# SlippiBoardRev2.net
KiCad netlist of a schematic drawn in EAGLE
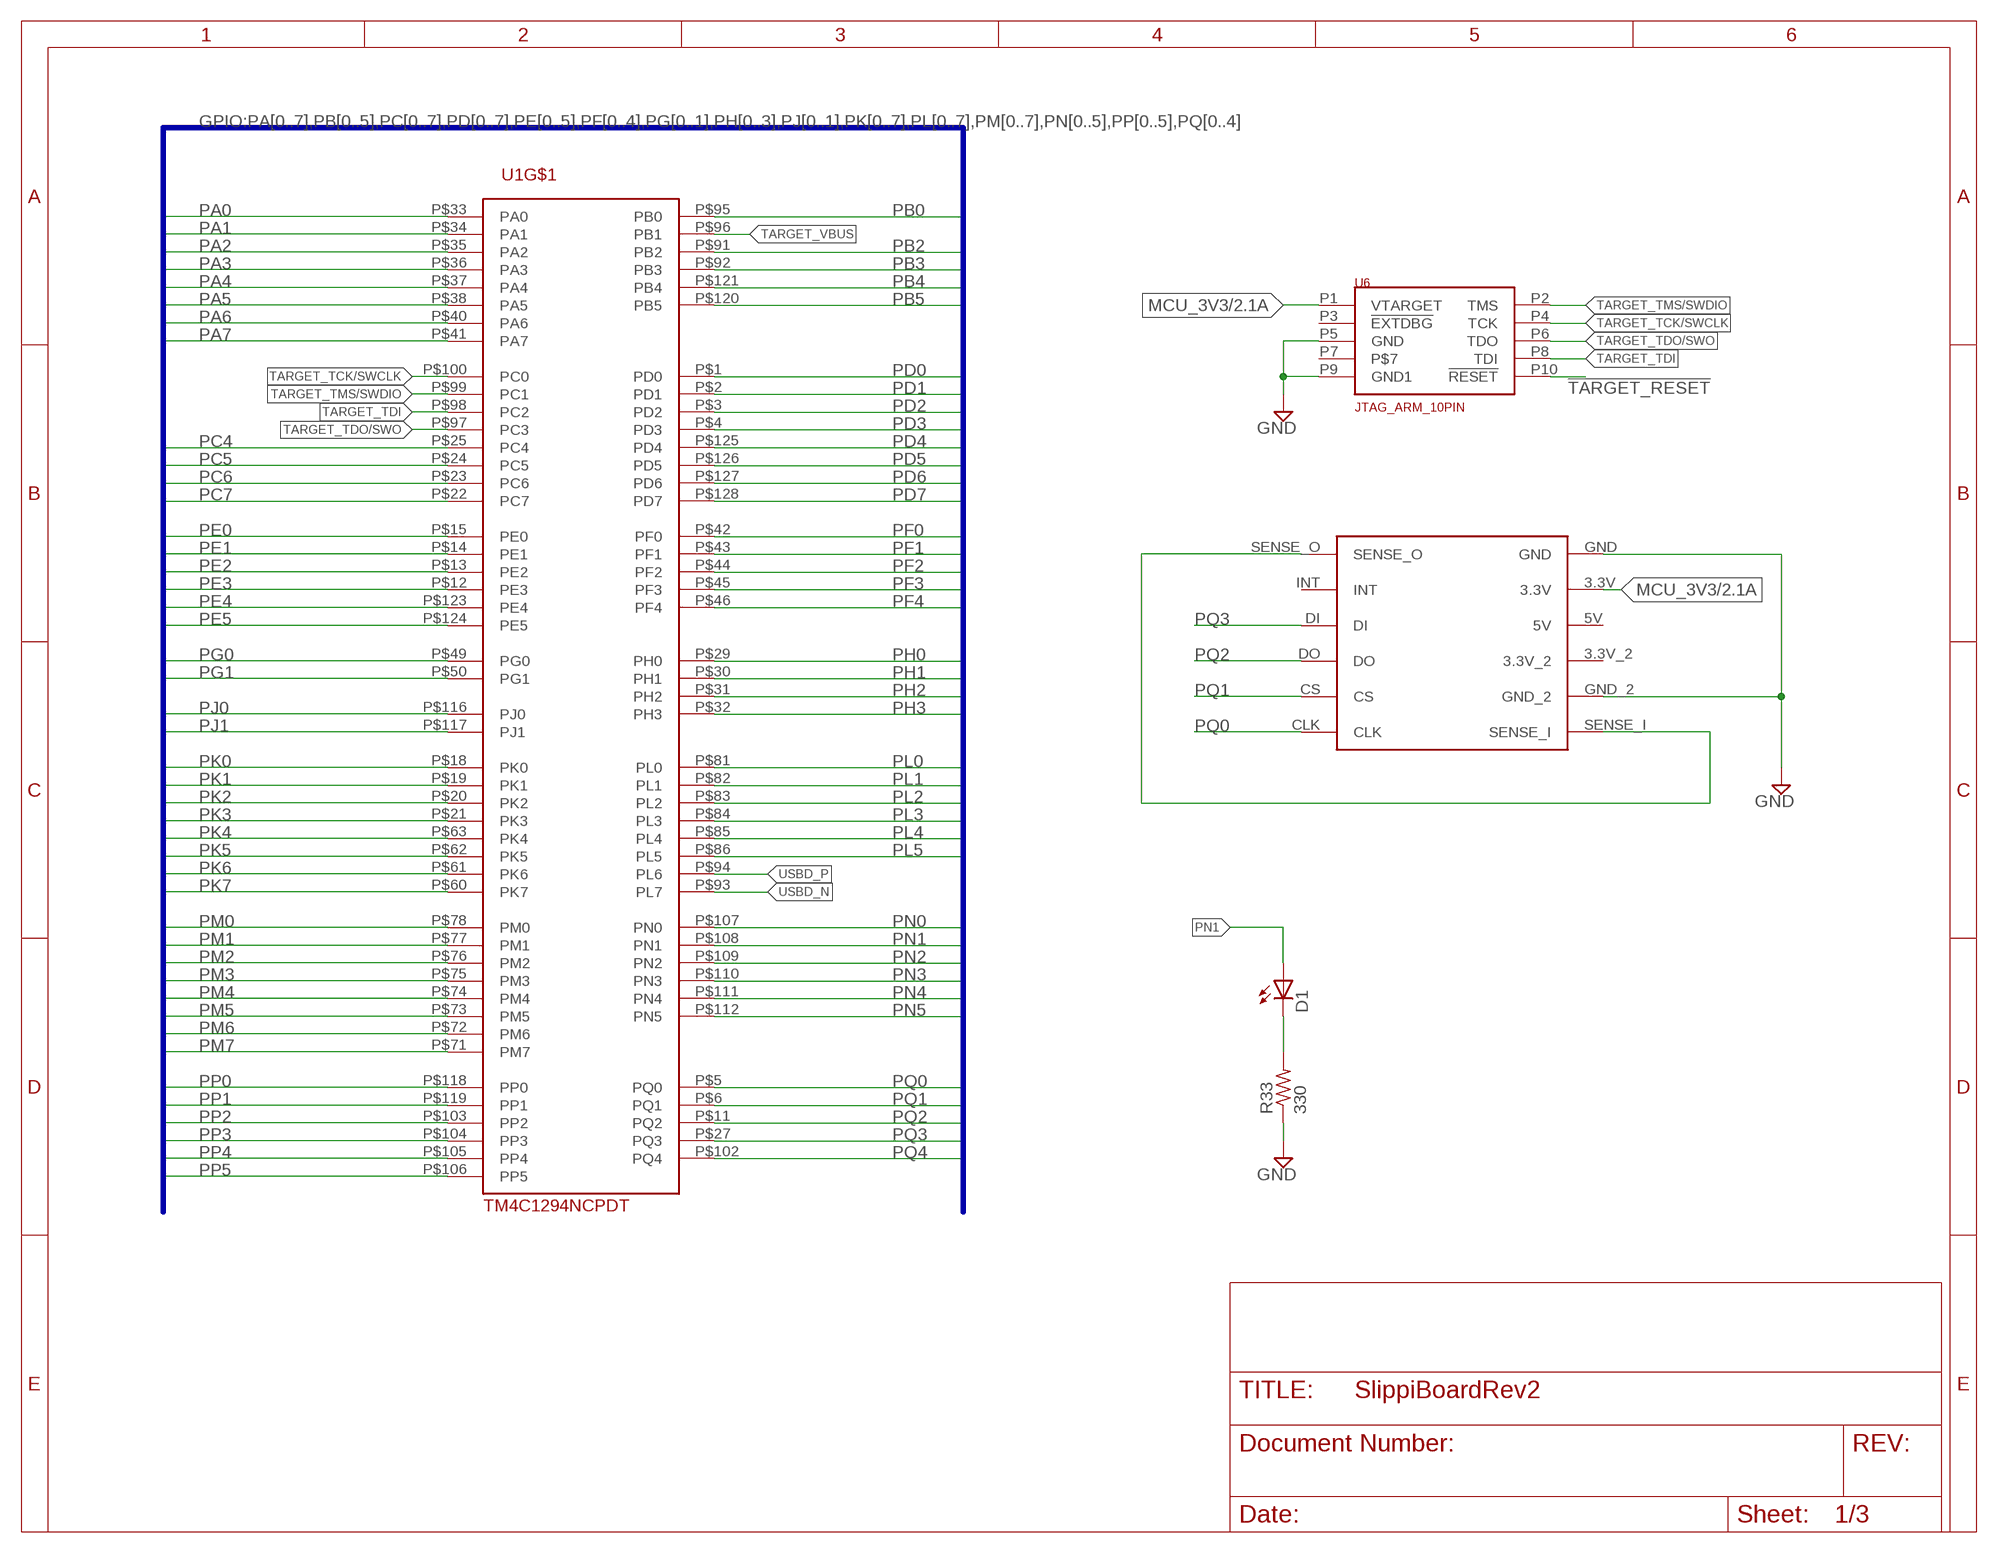
[diagram p0: schematic, sheet 1]
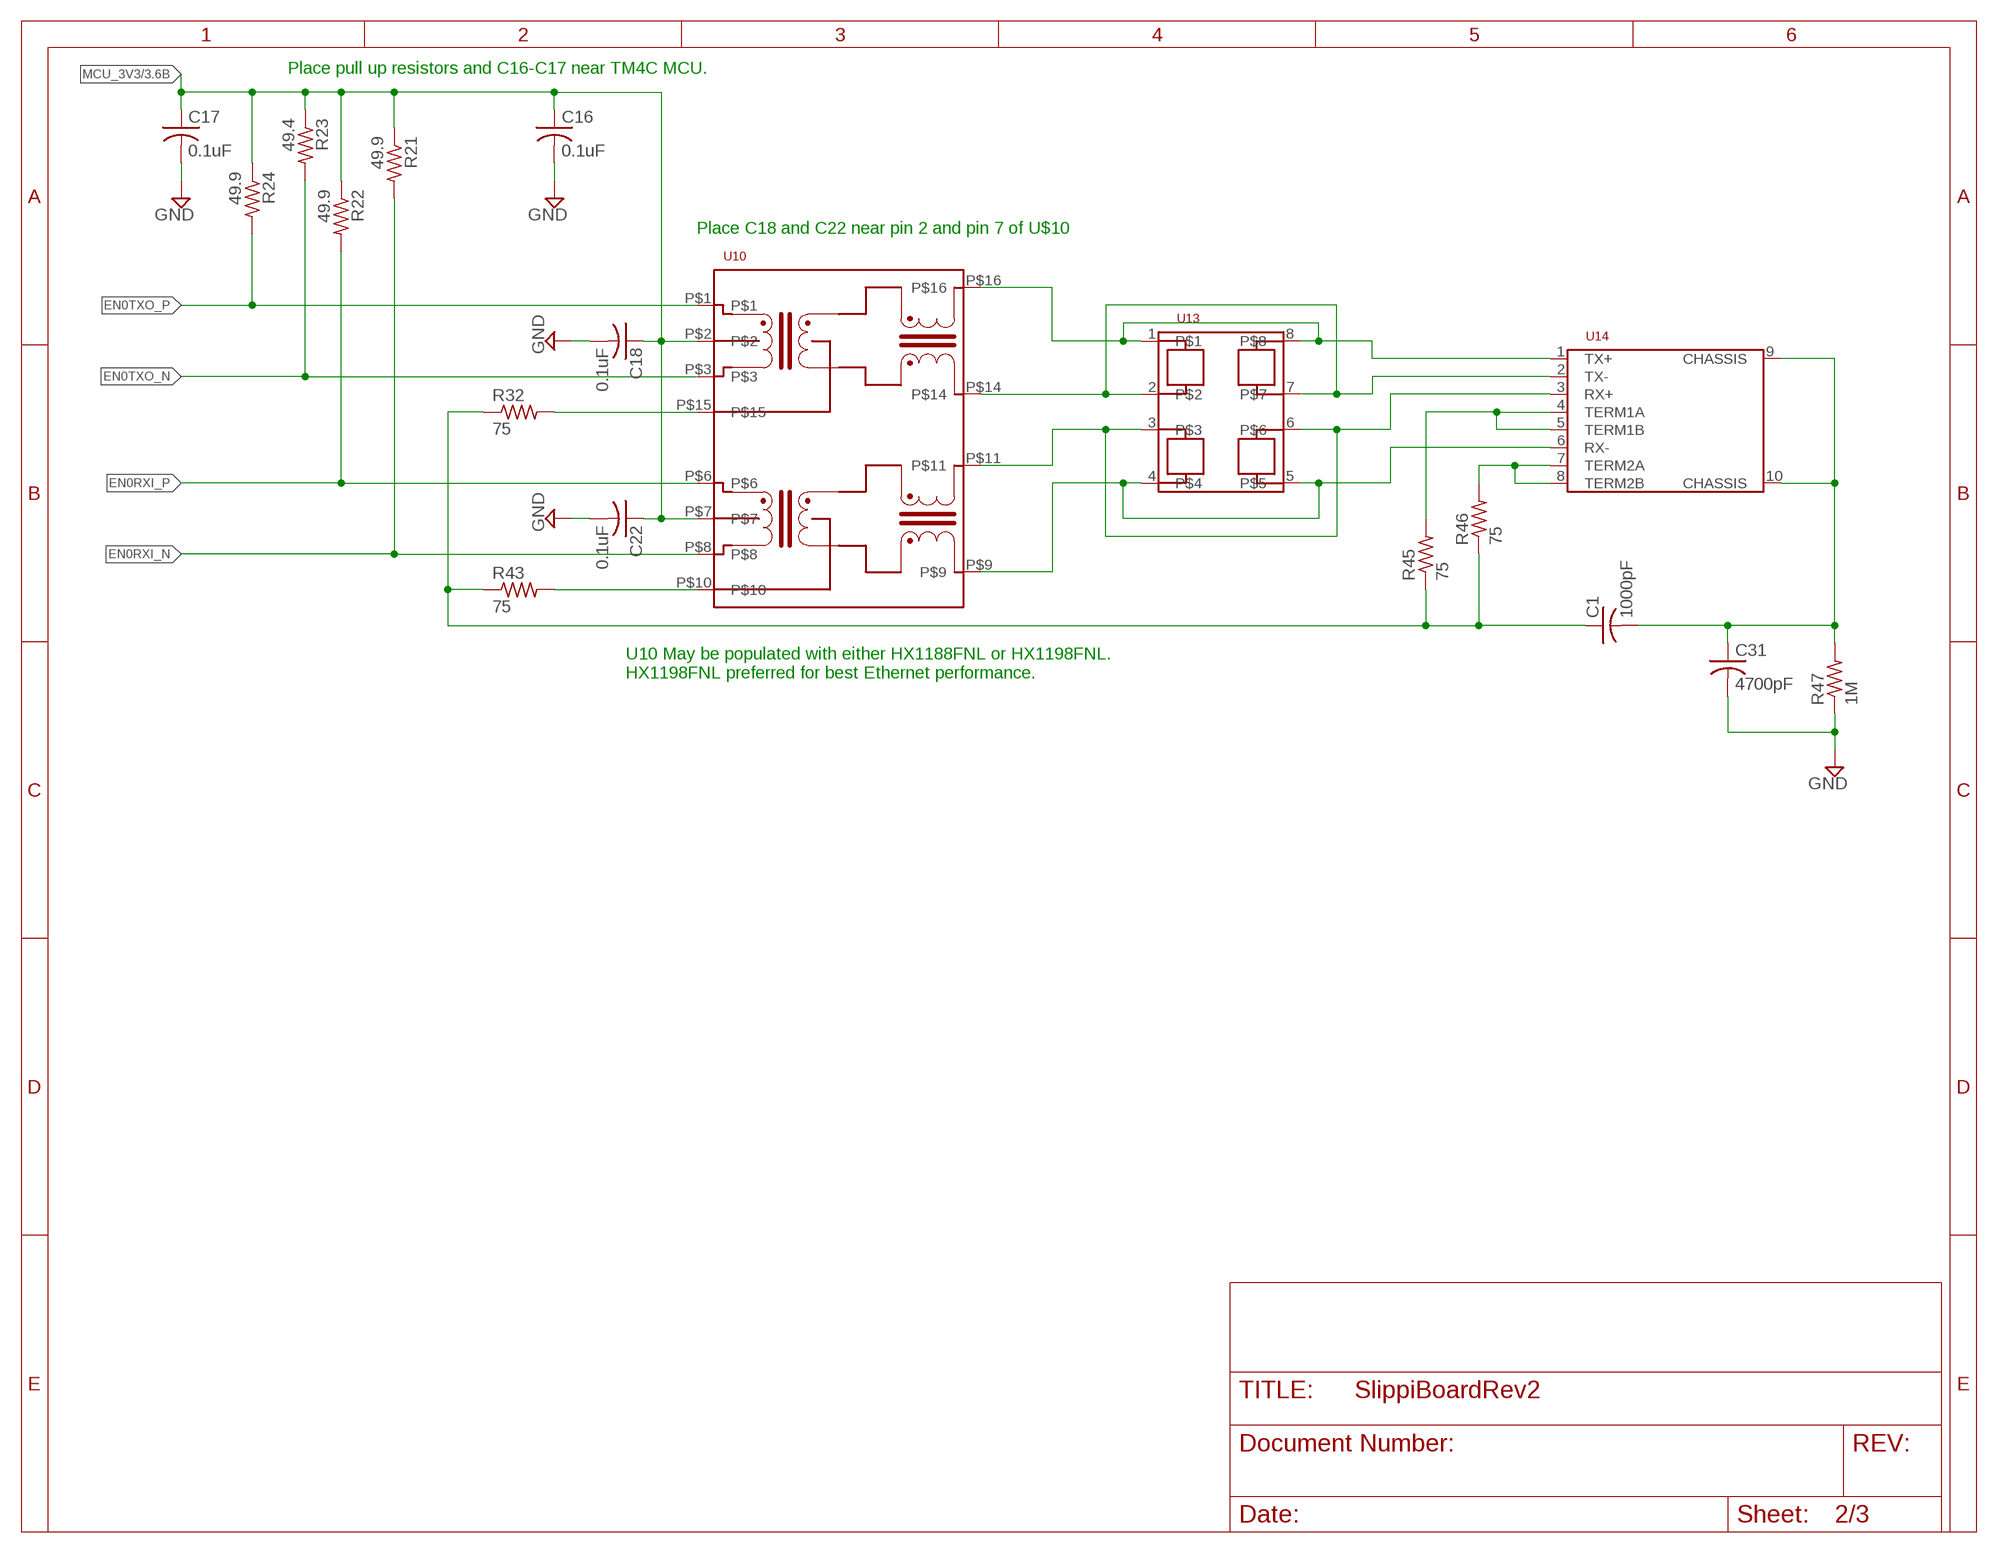
[diagram p1: schematic, sheet 2]
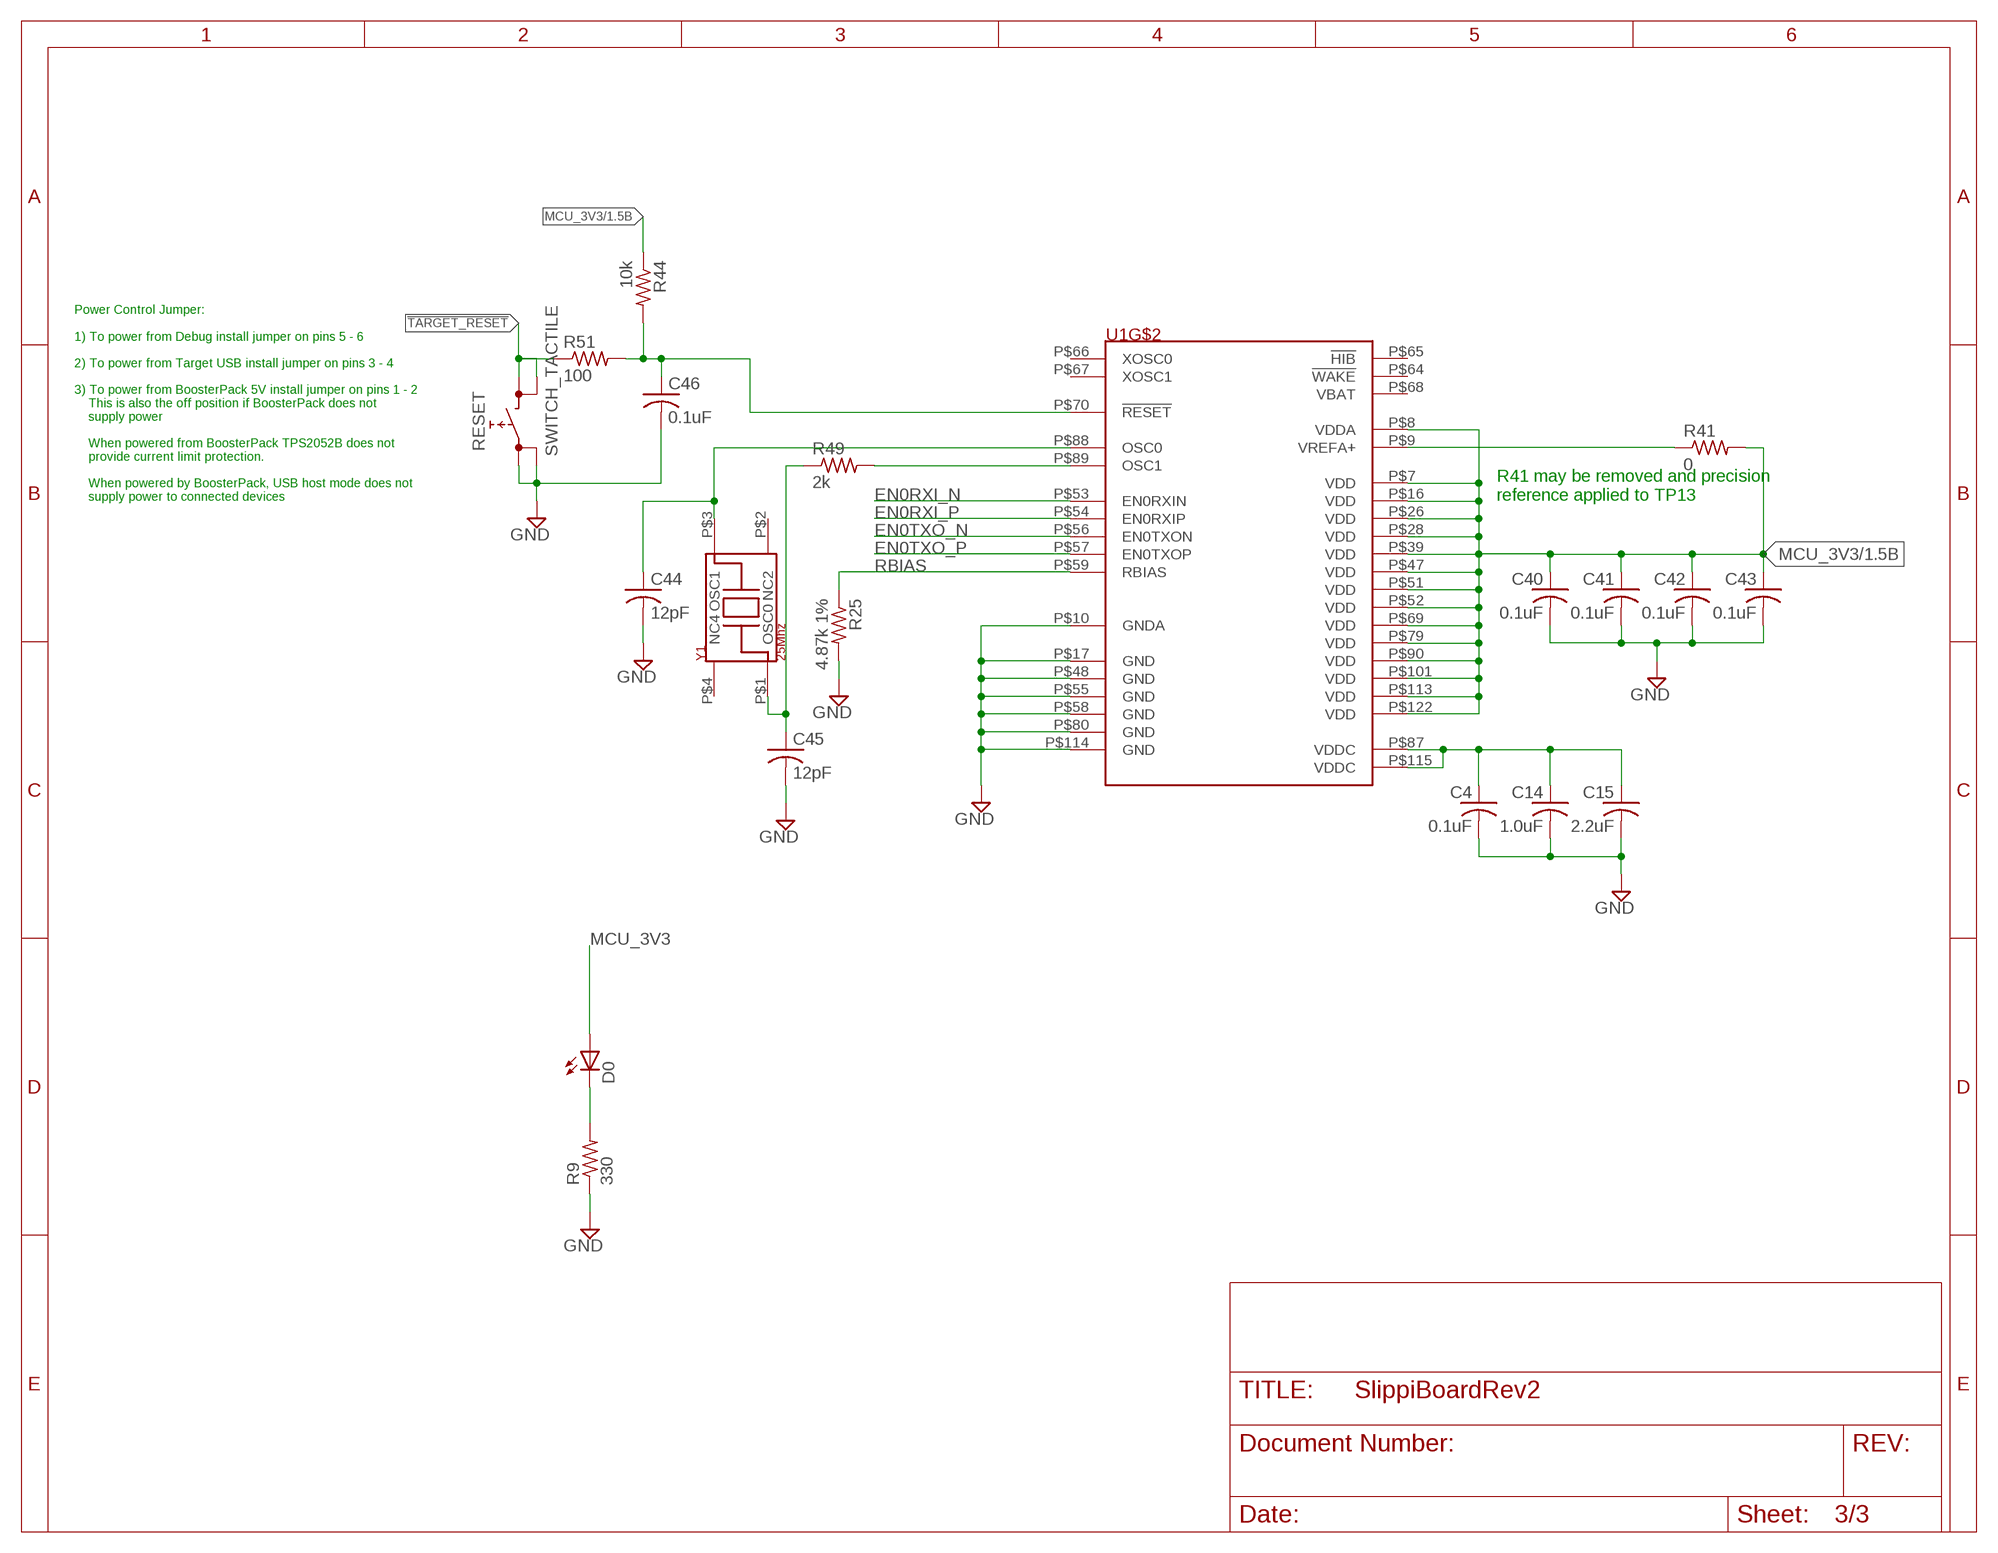
[diagram p2: schematic, sheet 3]

(export (version "E")
  (design (tool "Eeschema 10.0.6"))
  (components
    (comp (ref "C1")
      (value "1000pF")
      (footprint "eagle-import:C1210")
      (libsource (lib "eagle-import") (part "C-USC1210"))
    )
    (comp (ref "C16")
      (value "0.1uF")
      (footprint "eagle-import:C0402")
      (libsource (lib "eagle-import") (part "ek-tm4c129exl_C-USC0402"))
    )
    (comp (ref "C17")
      (value "0.1uF")
      (footprint "eagle-import:C0402")
      (libsource (lib "eagle-import") (part "ek-tm4c129exl_C-USC0402"))
    )
    (comp (ref "C18")
      (value "0.1uF")
      (footprint "eagle-import:C0402")
      (libsource (lib "eagle-import") (part "ek-tm4c129exl_C-USC0402"))
    )
    (comp (ref "C22")
      (value "0.1uF")
      (footprint "eagle-import:C0402")
      (libsource (lib "eagle-import") (part "ek-tm4c129exl_C-USC0402"))
    )
    (comp (ref "C31")
      (value "4700pF")
      (footprint "eagle-import:C1812")
      (libsource (lib "eagle-import") (part "ek-tm4c129exl_C-USC1812"))
    )
    (comp (ref "R21")
      (value "49.9")
      (footprint "eagle-import:R0402")
      (libsource (lib "eagle-import") (part "ek-tm4c129exl_R-US_R0402"))
    )
    (comp (ref "R22")
      (value "49.9")
      (footprint "eagle-import:R0402")
      (libsource (lib "eagle-import") (part "ek-tm4c129exl_R-US_R0402"))
    )
    (comp (ref "R23")
      (value "49.4")
      (footprint "eagle-import:R0402")
      (libsource (lib "eagle-import") (part "ek-tm4c129exl_R-US_R0402"))
    )
    (comp (ref "R24")
      (value "49.9")
      (footprint "eagle-import:R0402")
      (libsource (lib "eagle-import") (part "ek-tm4c129exl_R-US_R0402"))
    )
    (comp (ref "R32")
      (value "75")
      (footprint "eagle-import:R0402")
      (libsource (lib "eagle-import") (part "ek-tm4c129exl_R-US_R0402"))
    )
    (comp (ref "R43")
      (value "75")
      (footprint "eagle-import:R0402")
      (libsource (lib "eagle-import") (part "ek-tm4c129exl_R-US_R0402"))
    )
    (comp (ref "R45")
      (value "75")
      (footprint "eagle-import:R0402")
      (libsource (lib "eagle-import") (part "ek-tm4c129exl_R-US_R0402"))
    )
    (comp (ref "R46")
      (value "75")
      (footprint "eagle-import:R0402")
      (libsource (lib "eagle-import") (part "ek-tm4c129exl_R-US_R0402"))
    )
    (comp (ref "R47")
      (value "1M")
      (footprint "eagle-import:R1206")
      (libsource (lib "eagle-import") (part "R-US_R1206"))
    )
    (comp (ref "U10")
      (value "MAG_PULSE_HX1188FNL")
      (footprint "eagle-import:MAG_PULSE_HX1188FNL")
      (libsource (lib "eagle-import") (part "MAG_PULSE_HX1188FNL"))
    )
    (comp (ref "U13")
      (value "SLVU2.8-4")
      (footprint "eagle-import:D8")
      (libsource (lib "eagle-import") (part "SLVU2.8-4"))
    )
    (comp (ref "U14")
      (value "JACK_RJ45_NOMAG_NOLED_TECON")
      (footprint "eagle-import:RJ45_TE_CON_NOMAG_NOLED")
      (libsource (lib "eagle-import") (part "JACK_RJ45_NOMAG_NOLED_TECON"))
    )
    (comp (ref "D1")
      (value "LEDCHIPLED_0603")
      (footprint "eagle-import:CHIPLED_0603")
      (libsource (lib "eagle-import") (part "LEDCHIPLED_0603"))
    )
    (comp (ref "R33")
      (value "330")
      (footprint "eagle-import:R0402")
      (libsource (lib "eagle-import") (part "ek-tm4c129exl_R-US_R0402"))
    )
    (comp (ref "U$1")
      (value "GC_MEMCARD_CON")
      (footprint "eagle-import:GC_MEMCARD_CON")
      (libsource (lib "eagle-import") (part "GC_MEMCARD_CON"))
    )
    (comp (ref "U1")
      (value "TM4C1294NCPDT")
      (footprint "eagle-import:TQFP-128")
      (fields (field (name "GNUM") "G50-QF128-C1294-ALH"))
      (libsource (lib "eagle-import") (part "TM4C1294NCPDT"))
    )
    (comp (ref "U6")
      (value "JTAG_ARM_10PIN")
      (footprint "eagle-import:CON_2X5_50MIL")
      (libsource (lib "eagle-import") (part "JTAG_ARM_10PIN"))
    )
    (comp (ref "C4")
      (value "0.1uF")
      (footprint "eagle-import:C0402")
      (libsource (lib "eagle-import") (part "ek-tm4c129exl_C-USC0402"))
    )
    (comp (ref "C14")
      (value "1.0uF")
      (footprint "eagle-import:C0402")
      (libsource (lib "eagle-import") (part "ek-tm4c129exl_C-USC0402"))
    )
    (comp (ref "C15")
      (value "2.2uF")
      (footprint "eagle-import:C0603K")
      (fields (field (name "DIGIKEY_PARTNUM") "311-1451-2-ND"))
      (libsource (lib "eagle-import") (part "ek-tm4c129exl_C-USC0603K"))
    )
    (comp (ref "C40")
      (value "0.1uF")
      (footprint "eagle-import:C0402")
      (libsource (lib "eagle-import") (part "ek-tm4c129exl_C-USC0402"))
    )
    (comp (ref "C41")
      (value "0.1uF")
      (footprint "eagle-import:C0402")
      (libsource (lib "eagle-import") (part "ek-tm4c129exl_C-USC0402"))
    )
    (comp (ref "C42")
      (value "0.1uF")
      (footprint "eagle-import:C0402")
      (libsource (lib "eagle-import") (part "ek-tm4c129exl_C-USC0402"))
    )
    (comp (ref "C43")
      (value "0.1uF")
      (footprint "eagle-import:C0402")
      (libsource (lib "eagle-import") (part "ek-tm4c129exl_C-USC0402"))
    )
    (comp (ref "C44")
      (value "12pF")
      (footprint "eagle-import:C0402")
      (libsource (lib "eagle-import") (part "ek-tm4c129exl_C-USC0402"))
    )
    (comp (ref "C45")
      (value "12pF")
      (footprint "eagle-import:C0402")
      (libsource (lib "eagle-import") (part "ek-tm4c129exl_C-USC0402"))
    )
    (comp (ref "C46")
      (value "0.1uF")
      (footprint "eagle-import:C0402")
      (libsource (lib "eagle-import") (part "ek-tm4c129exl_C-USC0402"))
    )
    (comp (ref "D0")
      (value "LEDCHIPLED_0603")
      (footprint "eagle-import:CHIPLED_0603")
      (libsource (lib "eagle-import") (part "LEDCHIPLED_0603"))
    )
    (comp (ref "R9")
      (value "330")
      (footprint "eagle-import:R0402")
      (libsource (lib "eagle-import") (part "ek-tm4c129exl_R-US_R0402"))
    )
    (comp (ref "R25")
      (value "4.87k 1%")
      (footprint "eagle-import:R0402")
      (libsource (lib "eagle-import") (part "ek-tm4c129exl_R-US_R0402"))
    )
    (comp (ref "R41")
      (value "0")
      (footprint "eagle-import:R0402")
      (libsource (lib "eagle-import") (part "ek-tm4c129exl_R-US_R0402"))
    )
    (comp (ref "R44")
      (value "10k")
      (footprint "eagle-import:R0402")
      (libsource (lib "eagle-import") (part "ek-tm4c129exl_R-US_R0402"))
    )
    (comp (ref "R49")
      (value "2k")
      (footprint "eagle-import:R0402")
      (libsource (lib "eagle-import") (part "ek-tm4c129exl_R-US_R0402"))
    )
    (comp (ref "R51")
      (value "100")
      (footprint "eagle-import:R0402")
      (libsource (lib "eagle-import") (part "ek-tm4c129exl_R-US_R0402"))
    )
    (comp (ref "RESET")
      (value "SWITCH_TACTILE")
      (footprint "eagle-import:SWITCH_6MM_6MM_TE_CON_SMD")
      (libsource (lib "eagle-import") (part "SWITCH_TACTILE"))
    )
    (comp (ref "Y1")
      (value "25Mhz")
      (footprint "eagle-import:NDK3.2X2.5")
      (libsource (lib "eagle-import") (part "NX3225GA"))
    )
  )
  (nets
    (net (code "2") (name "EN0RXI_N") (class "Default")
      (node (ref "R21") (pin "2") (pinfunction "2_2") (pintype "passive"))
      (node (ref "U1") (pin "P$53") (pinfunction "EN0RXIN_P$53") (pintype "bidirectional"))
      (node (ref "U10") (pin "P$8") (pinfunction "P$8_P$8") (pintype "bidirectional"))
    )
    (net (code "3") (name "EN0RXI_P") (class "Default")
      (node (ref "R22") (pin "2") (pinfunction "2_2") (pintype "passive"))
      (node (ref "U1") (pin "P$54") (pinfunction "EN0RXIP_P$54") (pintype "bidirectional"))
      (node (ref "U10") (pin "P$6") (pinfunction "P$6_P$6") (pintype "bidirectional"))
    )
    (net (code "4") (name "EN0TXO_N") (class "Default")
      (node (ref "R23") (pin "2") (pinfunction "2_2") (pintype "passive"))
      (node (ref "U1") (pin "P$56") (pinfunction "EN0TXON_P$56") (pintype "bidirectional"))
      (node (ref "U10") (pin "P$3") (pinfunction "P$3_P$3") (pintype "bidirectional"))
    )
    (net (code "5") (name "EN0TXO_P") (class "Default")
      (node (ref "R24") (pin "2") (pinfunction "2_2") (pintype "passive"))
      (node (ref "U1") (pin "P$57") (pinfunction "EN0TXOP_P$57") (pintype "bidirectional"))
      (node (ref "U10") (pin "P$1") (pinfunction "P$1_P$1") (pintype "bidirectional"))
    )
    (net (code "6") (name "GND") (class "Default")
      (node (ref "C14") (pin "2") (pinfunction "2_2") (pintype "passive"))
      (node (ref "C15") (pin "2") (pinfunction "2_2") (pintype "passive"))
      (node (ref "C16") (pin "2") (pinfunction "2_2") (pintype "passive"))
      (node (ref "C17") (pin "2") (pinfunction "2_2") (pintype "passive"))
      (node (ref "C18") (pin "2") (pinfunction "2_2") (pintype "passive"))
      (node (ref "C22") (pin "2") (pinfunction "2_2") (pintype "passive"))
      (node (ref "C31") (pin "2") (pinfunction "2_2") (pintype "passive"))
      (node (ref "C4") (pin "2") (pinfunction "2_2") (pintype "passive"))
      (node (ref "C40") (pin "2") (pinfunction "2_2") (pintype "passive"))
      (node (ref "C41") (pin "2") (pinfunction "2_2") (pintype "passive"))
      (node (ref "C42") (pin "2") (pinfunction "2_2") (pintype "passive"))
      (node (ref "C43") (pin "2") (pinfunction "2_2") (pintype "passive"))
      (node (ref "C44") (pin "2") (pinfunction "2_2") (pintype "passive"))
      (node (ref "C45") (pin "2") (pinfunction "2_2") (pintype "passive"))
      (node (ref "C46") (pin "2") (pinfunction "2_2") (pintype "passive"))
      (node (ref "R25") (pin "2") (pinfunction "2_2") (pintype "passive"))
      (node (ref "R33") (pin "1") (pinfunction "1_1") (pintype "passive"))
      (node (ref "R47") (pin "1") (pinfunction "1_1") (pintype "passive"))
      (node (ref "R9") (pin "1") (pinfunction "1_1") (pintype "passive"))
      (node (ref "RESET") (pin "P$1") (pinfunction "0_P$1") (pintype "passive"))
      (node (ref "RESET") (pin "P$2") (pinfunction "0_P$2") (pintype "passive"))
      (node (ref "U$1") (pin "GND") (pinfunction "GND_GND") (pintype "bidirectional"))
      (node (ref "U$1") (pin "GND_2") (pinfunction "GND_2_GND_2") (pintype "bidirectional"))
      (node (ref "U1") (pin "P$10") (pinfunction "GNDA_P$10") (pintype "bidirectional"))
      (node (ref "U1") (pin "P$114") (pinfunction "GND_P$114") (pintype "bidirectional"))
      (node (ref "U1") (pin "P$17") (pinfunction "GND_P$17") (pintype "bidirectional"))
      (node (ref "U1") (pin "P$48") (pinfunction "GND_P$48") (pintype "bidirectional"))
      (node (ref "U1") (pin "P$55") (pinfunction "GND_P$55") (pintype "bidirectional"))
      (node (ref "U1") (pin "P$58") (pinfunction "GND_P$58") (pintype "bidirectional"))
      (node (ref "U1") (pin "P$80") (pinfunction "GND_P$80") (pintype "bidirectional"))
      (node (ref "U6") (pin "P5") (pinfunction "GND_P5") (pintype "bidirectional"))
      (node (ref "U6") (pin "P9") (pinfunction "GND1_P9") (pintype "bidirectional"))
    )
    (net (code "7") (name "MCU_3V3") (class "Default")
      (node (ref "C16") (pin "1") (pinfunction "1_1") (pintype "passive"))
      (node (ref "C17") (pin "1") (pinfunction "1_1") (pintype "passive"))
      (node (ref "C18") (pin "1") (pinfunction "1_1") (pintype "passive"))
      (node (ref "C22") (pin "1") (pinfunction "1_1") (pintype "passive"))
      (node (ref "C40") (pin "1") (pinfunction "1_1") (pintype "passive"))
      (node (ref "C41") (pin "1") (pinfunction "1_1") (pintype "passive"))
      (node (ref "C42") (pin "1") (pinfunction "1_1") (pintype "passive"))
      (node (ref "C43") (pin "1") (pinfunction "1_1") (pintype "passive"))
      (node (ref "D0") (pin "A") (pinfunction "A_A") (pintype "passive"))
      (node (ref "R21") (pin "1") (pinfunction "1_1") (pintype "passive"))
      (node (ref "R22") (pin "1") (pinfunction "1_1") (pintype "passive"))
      (node (ref "R23") (pin "1") (pinfunction "1_1") (pintype "passive"))
      (node (ref "R24") (pin "1") (pinfunction "1_1") (pintype "passive"))
      (node (ref "R41") (pin "2") (pinfunction "2_2") (pintype "passive"))
      (node (ref "R44") (pin "1") (pinfunction "1_1") (pintype "passive"))
      (node (ref "U$1") (pin "3.3V") (pinfunction "3.3V_3.3V") (pintype "bidirectional"))
      (node (ref "U1") (pin "P$101") (pinfunction "VDD_P$101") (pintype "bidirectional"))
      (node (ref "U1") (pin "P$113") (pinfunction "VDD_P$113") (pintype "bidirectional"))
      (node (ref "U1") (pin "P$122") (pinfunction "VDD_P$122") (pintype "bidirectional"))
      (node (ref "U1") (pin "P$16") (pinfunction "VDD_P$16") (pintype "bidirectional"))
      (node (ref "U1") (pin "P$26") (pinfunction "VDD_P$26") (pintype "bidirectional"))
      (node (ref "U1") (pin "P$28") (pinfunction "VDD_P$28") (pintype "bidirectional"))
      (node (ref "U1") (pin "P$39") (pinfunction "VDD_P$39") (pintype "bidirectional"))
      (node (ref "U1") (pin "P$47") (pinfunction "VDD_P$47") (pintype "bidirectional"))
      (node (ref "U1") (pin "P$51") (pinfunction "VDD_P$51") (pintype "bidirectional"))
      (node (ref "U1") (pin "P$52") (pinfunction "VDD_P$52") (pintype "bidirectional"))
      (node (ref "U1") (pin "P$69") (pinfunction "VDD_P$69") (pintype "bidirectional"))
      (node (ref "U1") (pin "P$7") (pinfunction "VDD_P$7") (pintype "bidirectional"))
      (node (ref "U1") (pin "P$79") (pinfunction "VDD_P$79") (pintype "bidirectional"))
      (node (ref "U1") (pin "P$8") (pinfunction "VDDA_P$8") (pintype "bidirectional"))
      (node (ref "U1") (pin "P$90") (pinfunction "VDD_P$90") (pintype "bidirectional"))
      (node (ref "U10") (pin "P$2") (pinfunction "P$2_P$2") (pintype "bidirectional"))
      (node (ref "U10") (pin "P$7") (pinfunction "P$7_P$7") (pintype "bidirectional"))
      (node (ref "U6") (pin "P1") (pinfunction "VTARGET_P1") (pintype "bidirectional"))
    )
    (net (code "8") (name "Net-(C1-Pad1)") (class "Default")
      (node (ref "C1") (pin "1") (pinfunction "1_1") (pintype "passive"))
      (node (ref "R32") (pin "1") (pinfunction "1_1") (pintype "passive"))
      (node (ref "R43") (pin "1") (pinfunction "1_1") (pintype "passive"))
      (node (ref "R45") (pin "1") (pinfunction "1_1") (pintype "passive"))
      (node (ref "R46") (pin "1") (pinfunction "1_1") (pintype "passive"))
    )
    (net (code "9") (name "Net-(C1-Pad2)") (class "Default")
      (node (ref "C1") (pin "2") (pinfunction "2_2") (pintype "passive"))
      (node (ref "C31") (pin "1") (pinfunction "1_1") (pintype "passive"))
      (node (ref "R47") (pin "2") (pinfunction "2_2") (pintype "passive"))
      (node (ref "U14") (pin "10") (pinfunction "CHASSIS_10") (pintype "bidirectional"))
      (node (ref "U14") (pin "9") (pinfunction "CHASSIS_9") (pintype "bidirectional"))
    )
    (net (code "10") (name "Net-(C14-Pad1)") (class "Default")
      (node (ref "C14") (pin "1") (pinfunction "1_1") (pintype "passive"))
      (node (ref "C15") (pin "1") (pinfunction "1_1") (pintype "passive"))
      (node (ref "C4") (pin "1") (pinfunction "1_1") (pintype "passive"))
      (node (ref "U1") (pin "P$115") (pinfunction "VDDC_P$115") (pintype "bidirectional"))
      (node (ref "U1") (pin "P$87") (pinfunction "VDDC_P$87") (pintype "bidirectional"))
    )
    (net (code "11") (name "Net-(D0-PadC)") (class "Default")
      (node (ref "D0") (pin "C") (pinfunction "C_C") (pintype "passive"))
      (node (ref "R9") (pin "2") (pinfunction "2_2") (pintype "passive"))
    )
    (net (code "12") (name "Net-(D1-PadC)") (class "Default")
      (node (ref "D1") (pin "C") (pinfunction "C_C") (pintype "passive"))
      (node (ref "R33") (pin "2") (pinfunction "2_2") (pintype "passive"))
    )
    (net (code "13") (name "Net-(R32-Pad2)") (class "Default")
      (node (ref "R32") (pin "2") (pinfunction "2_2") (pintype "passive"))
      (node (ref "U10") (pin "P$15") (pinfunction "P$15_P$15") (pintype "bidirectional"))
    )
    (net (code "14") (name "Net-(R43-Pad2)") (class "Default")
      (node (ref "R43") (pin "2") (pinfunction "2_2") (pintype "passive"))
      (node (ref "U10") (pin "P$10") (pinfunction "P$10_P$10") (pintype "bidirectional"))
    )
    (net (code "15") (name "Net-(U$1-PadSENSE_I)") (class "Default")
      (node (ref "U$1") (pin "SENSE_I") (pinfunction "SENSE_I_SENSE_I") (pintype "bidirectional"))
      (node (ref "U$1") (pin "SENSE_O") (pinfunction "SENSE_O_SENSE_O") (pintype "bidirectional"))
    )
    (net (code "16") (name "Net-(U1B-OSC0)") (class "Default")
      (node (ref "C44") (pin "1") (pinfunction "1_1") (pintype "passive"))
      (node (ref "U1") (pin "P$88") (pinfunction "OSC0_P$88") (pintype "bidirectional"))
      (node (ref "Y1") (pin "P$3") (pinfunction "OSC1_P$3") (pintype "bidirectional"))
    )
    (net (code "17") (name "Net-(U1B-OSC1)") (class "Default")
      (node (ref "R49") (pin "2") (pinfunction "2_2") (pintype "passive"))
      (node (ref "U1") (pin "P$89") (pinfunction "OSC1_P$89") (pintype "bidirectional"))
    )
    (net (code "18") (name "Net-(U1B-VREFA+)") (class "Default")
      (node (ref "R41") (pin "1") (pinfunction "1_1") (pintype "passive"))
      (node (ref "U1") (pin "P$9") (pinfunction "VREFA+_P$9") (pintype "bidirectional"))
    )
    (net (code "19") (name "Net-(U1B-~{RESET})") (class "Default")
      (node (ref "C46") (pin "1") (pinfunction "1_1") (pintype "passive"))
      (node (ref "R44") (pin "2") (pinfunction "2_2") (pintype "passive"))
      (node (ref "R51") (pin "2") (pinfunction "2_2") (pintype "passive"))
      (node (ref "U1") (pin "P$70") (pinfunction "~{RESET}_P$70") (pintype "bidirectional"))
    )
    (net (code "20") (name "Net-(U13-P$1)") (class "Default")
      (node (ref "U10") (pin "P$16") (pinfunction "P$16_P$16") (pintype "bidirectional"))
      (node (ref "U13") (pin "1") (pinfunction "P$1_1") (pintype "bidirectional"))
      (node (ref "U13") (pin "8") (pinfunction "P$8_8") (pintype "bidirectional"))
      (node (ref "U14") (pin "1") (pinfunction "TX+_1") (pintype "bidirectional"))
    )
    (net (code "21") (name "Net-(U13-P$2)") (class "Default")
      (node (ref "U10") (pin "P$14") (pinfunction "P$14_P$14") (pintype "bidirectional"))
      (node (ref "U13") (pin "2") (pinfunction "P$2_2") (pintype "bidirectional"))
      (node (ref "U13") (pin "7") (pinfunction "P$7_7") (pintype "bidirectional"))
      (node (ref "U14") (pin "2") (pinfunction "TX-_2") (pintype "bidirectional"))
    )
    (net (code "22") (name "Net-(U13-P$3)") (class "Default")
      (node (ref "U10") (pin "P$11") (pinfunction "P$11_P$11") (pintype "bidirectional"))
      (node (ref "U13") (pin "3") (pinfunction "P$3_3") (pintype "bidirectional"))
      (node (ref "U13") (pin "6") (pinfunction "P$6_6") (pintype "bidirectional"))
      (node (ref "U14") (pin "3") (pinfunction "RX+_3") (pintype "bidirectional"))
    )
    (net (code "23") (name "Net-(U13-P$4)") (class "Default")
      (node (ref "U10") (pin "P$9") (pinfunction "P$9_P$9") (pintype "bidirectional"))
      (node (ref "U13") (pin "4") (pinfunction "P$4_4") (pintype "bidirectional"))
      (node (ref "U13") (pin "5") (pinfunction "P$5_5") (pintype "bidirectional"))
      (node (ref "U14") (pin "6") (pinfunction "RX-_6") (pintype "bidirectional"))
    )
    (net (code "24") (name "Net-(U14-TERM1A)") (class "Default")
      (node (ref "R45") (pin "2") (pinfunction "2_2") (pintype "passive"))
      (node (ref "U14") (pin "4") (pinfunction "TERM1A_4") (pintype "bidirectional"))
      (node (ref "U14") (pin "5") (pinfunction "TERM1B_5") (pintype "bidirectional"))
    )
    (net (code "25") (name "Net-(U14-TERM2A)") (class "Default")
      (node (ref "R46") (pin "2") (pinfunction "2_2") (pintype "passive"))
      (node (ref "U14") (pin "7") (pinfunction "TERM2A_7") (pintype "bidirectional"))
      (node (ref "U14") (pin "8") (pinfunction "TERM2B_8") (pintype "bidirectional"))
    )
    (net (code "26") (name "Net-(Y1-OSC0)") (class "Default")
      (node (ref "C45") (pin "1") (pinfunction "1_1") (pintype "passive"))
      (node (ref "R49") (pin "1") (pinfunction "1_1") (pintype "passive"))
      (node (ref "Y1") (pin "P$1") (pinfunction "OSC0_P$1") (pintype "bidirectional"))
    )
    (net (code "27") (name "PA0") (class "Default")
      (node (ref "U1") (pin "P$33") (pinfunction "PA0_P$33") (pintype "bidirectional"))
    )
    (net (code "28") (name "PA1") (class "Default")
      (node (ref "U1") (pin "P$34") (pinfunction "PA1_P$34") (pintype "bidirectional"))
    )
    (net (code "29") (name "PA2") (class "Default")
      (node (ref "U1") (pin "P$35") (pinfunction "PA2_P$35") (pintype "bidirectional"))
    )
    (net (code "30") (name "PA3") (class "Default")
      (node (ref "U1") (pin "P$36") (pinfunction "PA3_P$36") (pintype "bidirectional"))
    )
    (net (code "31") (name "PA4") (class "Default")
      (node (ref "U1") (pin "P$37") (pinfunction "PA4_P$37") (pintype "bidirectional"))
    )
    (net (code "32") (name "PA5") (class "Default")
      (node (ref "U1") (pin "P$38") (pinfunction "PA5_P$38") (pintype "bidirectional"))
    )
    (net (code "33") (name "PA6") (class "Default")
      (node (ref "U1") (pin "P$40") (pinfunction "PA6_P$40") (pintype "bidirectional"))
    )
    (net (code "34") (name "PA7") (class "Default")
      (node (ref "U1") (pin "P$41") (pinfunction "PA7_P$41") (pintype "bidirectional"))
    )
    (net (code "35") (name "PB0") (class "Default")
      (node (ref "U1") (pin "P$95") (pinfunction "PB0_P$95") (pintype "bidirectional"))
    )
    (net (code "36") (name "PB2") (class "Default")
      (node (ref "U1") (pin "P$91") (pinfunction "PB2_P$91") (pintype "bidirectional"))
    )
    (net (code "37") (name "PB3") (class "Default")
      (node (ref "U1") (pin "P$92") (pinfunction "PB3_P$92") (pintype "bidirectional"))
    )
    (net (code "38") (name "PB4") (class "Default")
      (node (ref "U1") (pin "P$121") (pinfunction "PB4_P$121") (pintype "bidirectional"))
    )
    (net (code "39") (name "PB5") (class "Default")
      (node (ref "U1") (pin "P$120") (pinfunction "PB5_P$120") (pintype "bidirectional"))
    )
    (net (code "40") (name "PC4") (class "Default")
      (node (ref "U1") (pin "P$25") (pinfunction "PC4_P$25") (pintype "bidirectional"))
    )
    (net (code "41") (name "PC5") (class "Default")
      (node (ref "U1") (pin "P$24") (pinfunction "PC5_P$24") (pintype "bidirectional"))
    )
    (net (code "42") (name "PC6") (class "Default")
      (node (ref "U1") (pin "P$23") (pinfunction "PC6_P$23") (pintype "bidirectional"))
    )
    (net (code "43") (name "PC7") (class "Default")
      (node (ref "U1") (pin "P$22") (pinfunction "PC7_P$22") (pintype "bidirectional"))
    )
    (net (code "44") (name "PD0") (class "Default")
      (node (ref "U1") (pin "P$1") (pinfunction "PD0_P$1") (pintype "bidirectional"))
    )
    (net (code "45") (name "PD1") (class "Default")
      (node (ref "U1") (pin "P$2") (pinfunction "PD1_P$2") (pintype "bidirectional"))
    )
    (net (code "46") (name "PD2") (class "Default")
      (node (ref "U1") (pin "P$3") (pinfunction "PD2_P$3") (pintype "bidirectional"))
    )
    (net (code "47") (name "PD3") (class "Default")
      (node (ref "U1") (pin "P$4") (pinfunction "PD3_P$4") (pintype "bidirectional"))
    )
    (net (code "48") (name "PD4") (class "Default")
      (node (ref "U1") (pin "P$125") (pinfunction "PD4_P$125") (pintype "bidirectional"))
    )
    (net (code "49") (name "PD5") (class "Default")
      (node (ref "U1") (pin "P$126") (pinfunction "PD5_P$126") (pintype "bidirectional"))
    )
    (net (code "50") (name "PD6") (class "Default")
      (node (ref "U1") (pin "P$127") (pinfunction "PD6_P$127") (pintype "bidirectional"))
    )
    (net (code "51") (name "PD7") (class "Default")
      (node (ref "U1") (pin "P$128") (pinfunction "PD7_P$128") (pintype "bidirectional"))
    )
    (net (code "52") (name "PE0") (class "Default")
      (node (ref "U1") (pin "P$15") (pinfunction "PE0_P$15") (pintype "bidirectional"))
    )
    (net (code "53") (name "PE1") (class "Default")
      (node (ref "U1") (pin "P$14") (pinfunction "PE1_P$14") (pintype "bidirectional"))
    )
    (net (code "54") (name "PE2") (class "Default")
      (node (ref "U1") (pin "P$13") (pinfunction "PE2_P$13") (pintype "bidirectional"))
    )
    (net (code "55") (name "PE3") (class "Default")
      (node (ref "U1") (pin "P$12") (pinfunction "PE3_P$12") (pintype "bidirectional"))
    )
    (net (code "56") (name "PE4") (class "Default")
      (node (ref "U1") (pin "P$123") (pinfunction "PE4_P$123") (pintype "bidirectional"))
    )
    (net (code "57") (name "PE5") (class "Default")
      (node (ref "U1") (pin "P$124") (pinfunction "PE5_P$124") (pintype "bidirectional"))
    )
    (net (code "58") (name "PF0") (class "Default")
      (node (ref "U1") (pin "P$42") (pinfunction "PF0_P$42") (pintype "bidirectional"))
    )
    (net (code "59") (name "PF1") (class "Default")
      (node (ref "U1") (pin "P$43") (pinfunction "PF1_P$43") (pintype "bidirectional"))
    )
    (net (code "60") (name "PF2") (class "Default")
      (node (ref "U1") (pin "P$44") (pinfunction "PF2_P$44") (pintype "bidirectional"))
    )
    (net (code "61") (name "PF3") (class "Default")
      (node (ref "U1") (pin "P$45") (pinfunction "PF3_P$45") (pintype "bidirectional"))
    )
    (net (code "62") (name "PF4") (class "Default")
      (node (ref "U1") (pin "P$46") (pinfunction "PF4_P$46") (pintype "bidirectional"))
    )
    (net (code "63") (name "PG0") (class "Default")
      (node (ref "U1") (pin "P$49") (pinfunction "PG0_P$49") (pintype "bidirectional"))
    )
    (net (code "64") (name "PG1") (class "Default")
      (node (ref "U1") (pin "P$50") (pinfunction "PG1_P$50") (pintype "bidirectional"))
    )
    (net (code "65") (name "PH0") (class "Default")
      (node (ref "U1") (pin "P$29") (pinfunction "PH0_P$29") (pintype "bidirectional"))
    )
    (net (code "66") (name "PH1") (class "Default")
      (node (ref "U1") (pin "P$30") (pinfunction "PH1_P$30") (pintype "bidirectional"))
    )
    (net (code "67") (name "PH2") (class "Default")
      (node (ref "U1") (pin "P$31") (pinfunction "PH2_P$31") (pintype "bidirectional"))
    )
    (net (code "68") (name "PH3") (class "Default")
      (node (ref "U1") (pin "P$32") (pinfunction "PH3_P$32") (pintype "bidirectional"))
    )
    (net (code "69") (name "PJ0") (class "Default")
      (node (ref "U1") (pin "P$116") (pinfunction "PJ0_P$116") (pintype "bidirectional"))
    )
    (net (code "70") (name "PJ1") (class "Default")
      (node (ref "U1") (pin "P$117") (pinfunction "PJ1_P$117") (pintype "bidirectional"))
    )
    (net (code "71") (name "PK0") (class "Default")
      (node (ref "U1") (pin "P$18") (pinfunction "PK0_P$18") (pintype "bidirectional"))
    )
    (net (code "72") (name "PK1") (class "Default")
      (node (ref "U1") (pin "P$19") (pinfunction "PK1_P$19") (pintype "bidirectional"))
    )
    (net (code "73") (name "PK2") (class "Default")
      (node (ref "U1") (pin "P$20") (pinfunction "PK2_P$20") (pintype "bidirectional"))
    )
    (net (code "74") (name "PK3") (class "Default")
      (node (ref "U1") (pin "P$21") (pinfunction "PK3_P$21") (pintype "bidirectional"))
    )
    (net (code "75") (name "PK4") (class "Default")
      (node (ref "U1") (pin "P$63") (pinfunction "PK4_P$63") (pintype "bidirectional"))
    )
    (net (code "76") (name "PK5") (class "Default")
      (node (ref "U1") (pin "P$62") (pinfunction "PK5_P$62") (pintype "bidirectional"))
    )
    (net (code "77") (name "PK6") (class "Default")
      (node (ref "U1") (pin "P$61") (pinfunction "PK6_P$61") (pintype "bidirectional"))
    )
    (net (code "78") (name "PK7") (class "Default")
      (node (ref "U1") (pin "P$60") (pinfunction "PK7_P$60") (pintype "bidirectional"))
    )
    (net (code "79") (name "PL0") (class "Default")
      (node (ref "U1") (pin "P$81") (pinfunction "PL0_P$81") (pintype "bidirectional"))
    )
    (net (code "80") (name "PL1") (class "Default")
      (node (ref "U1") (pin "P$82") (pinfunction "PL1_P$82") (pintype "bidirectional"))
    )
    (net (code "81") (name "PL2") (class "Default")
      (node (ref "U1") (pin "P$83") (pinfunction "PL2_P$83") (pintype "bidirectional"))
    )
    (net (code "82") (name "PL3") (class "Default")
      (node (ref "U1") (pin "P$84") (pinfunction "PL3_P$84") (pintype "bidirectional"))
    )
    (net (code "83") (name "PL4") (class "Default")
      (node (ref "U1") (pin "P$85") (pinfunction "PL4_P$85") (pintype "bidirectional"))
    )
    (net (code "84") (name "PL5") (class "Default")
      (node (ref "U1") (pin "P$86") (pinfunction "PL5_P$86") (pintype "bidirectional"))
    )
    (net (code "85") (name "PM0") (class "Default")
      (node (ref "U1") (pin "P$78") (pinfunction "PM0_P$78") (pintype "bidirectional"))
    )
    (net (code "86") (name "PM1") (class "Default")
      (node (ref "U1") (pin "P$77") (pinfunction "PM1_P$77") (pintype "bidirectional"))
    )
    (net (code "87") (name "PM2") (class "Default")
      (node (ref "U1") (pin "P$76") (pinfunction "PM2_P$76") (pintype "bidirectional"))
    )
    (net (code "88") (name "PM3") (class "Default")
      (node (ref "U1") (pin "P$75") (pinfunction "PM3_P$75") (pintype "bidirectional"))
    )
    (net (code "89") (name "PM4") (class "Default")
      (node (ref "U1") (pin "P$74") (pinfunction "PM4_P$74") (pintype "bidirectional"))
    )
    (net (code "90") (name "PM5") (class "Default")
      (node (ref "U1") (pin "P$73") (pinfunction "PM5_P$73") (pintype "bidirectional"))
    )
    (net (code "91") (name "PM6") (class "Default")
      (node (ref "U1") (pin "P$72") (pinfunction "PM6_P$72") (pintype "bidirectional"))
    )
    (net (code "92") (name "PM7") (class "Default")
      (node (ref "U1") (pin "P$71") (pinfunction "PM7_P$71") (pintype "bidirectional"))
    )
    (net (code "93") (name "PN0") (class "Default")
      (node (ref "U1") (pin "P$107") (pinfunction "PN0_P$107") (pintype "bidirectional"))
    )
    (net (code "94") (name "PN1") (class "Default")
      (node (ref "D1") (pin "A") (pinfunction "A_A") (pintype "passive"))
      (node (ref "U1") (pin "P$108") (pinfunction "PN1_P$108") (pintype "bidirectional"))
    )
    (net (code "95") (name "PN2") (class "Default")
      (node (ref "U1") (pin "P$109") (pinfunction "PN2_P$109") (pintype "bidirectional"))
    )
    (net (code "96") (name "PN3") (class "Default")
      (node (ref "U1") (pin "P$110") (pinfunction "PN3_P$110") (pintype "bidirectional"))
    )
    (net (code "97") (name "PN4") (class "Default")
      (node (ref "U1") (pin "P$111") (pinfunction "PN4_P$111") (pintype "bidirectional"))
    )
    (net (code "98") (name "PN5") (class "Default")
      (node (ref "U1") (pin "P$112") (pinfunction "PN5_P$112") (pintype "bidirectional"))
    )
    (net (code "99") (name "PP0") (class "Default")
      (node (ref "U1") (pin "P$118") (pinfunction "PP0_P$118") (pintype "bidirectional"))
    )
    (net (code "100") (name "PP1") (class "Default")
      (node (ref "U1") (pin "P$119") (pinfunction "PP1_P$119") (pintype "bidirectional"))
    )
    (net (code "101") (name "PP2") (class "Default")
      (node (ref "U1") (pin "P$103") (pinfunction "PP2_P$103") (pintype "bidirectional"))
    )
    (net (code "102") (name "PP3") (class "Default")
      (node (ref "U1") (pin "P$104") (pinfunction "PP3_P$104") (pintype "bidirectional"))
    )
    (net (code "103") (name "PP4") (class "Default")
      (node (ref "U1") (pin "P$105") (pinfunction "PP4_P$105") (pintype "bidirectional"))
    )
    (net (code "104") (name "PP5") (class "Default")
      (node (ref "U1") (pin "P$106") (pinfunction "PP5_P$106") (pintype "bidirectional"))
    )
    (net (code "105") (name "PQ0") (class "Default")
      (node (ref "U$1") (pin "CLK") (pinfunction "CLK_CLK") (pintype "bidirectional"))
      (node (ref "U1") (pin "P$5") (pinfunction "PQ0_P$5") (pintype "bidirectional"))
    )
    (net (code "106") (name "PQ1") (class "Default")
      (node (ref "U$1") (pin "CS") (pinfunction "CS_CS") (pintype "bidirectional"))
      (node (ref "U1") (pin "P$6") (pinfunction "PQ1_P$6") (pintype "bidirectional"))
    )
    (net (code "107") (name "PQ2") (class "Default")
      (node (ref "U$1") (pin "DO") (pinfunction "DO_DO") (pintype "bidirectional"))
      (node (ref "U1") (pin "P$11") (pinfunction "PQ2_P$11") (pintype "bidirectional"))
    )
    (net (code "108") (name "PQ3") (class "Default")
      (node (ref "U$1") (pin "DI") (pinfunction "DI_DI") (pintype "bidirectional"))
      (node (ref "U1") (pin "P$27") (pinfunction "PQ3_P$27") (pintype "bidirectional"))
    )
    (net (code "109") (name "PQ4") (class "Default")
      (node (ref "U1") (pin "P$102") (pinfunction "PQ4_P$102") (pintype "bidirectional"))
    )
    (net (code "110") (name "RBIAS") (class "Default")
      (node (ref "R25") (pin "1") (pinfunction "1_1") (pintype "passive"))
      (node (ref "U1") (pin "P$59") (pinfunction "RBIAS_P$59") (pintype "bidirectional"))
    )
    (net (code "111") (name "TARGET_TCK{slash}SWCLK") (class "Default")
      (node (ref "U1") (pin "P$100") (pinfunction "PC0_P$100") (pintype "bidirectional"))
      (node (ref "U6") (pin "P4") (pinfunction "TCK_P4") (pintype "bidirectional"))
    )
    (net (code "112") (name "TARGET_TDI") (class "Default")
      (node (ref "U1") (pin "P$98") (pinfunction "PC2_P$98") (pintype "bidirectional"))
      (node (ref "U6") (pin "P8") (pinfunction "TDI_P8") (pintype "bidirectional"))
    )
    (net (code "113") (name "TARGET_TDO{slash}SWO") (class "Default")
      (node (ref "U1") (pin "P$97") (pinfunction "PC3_P$97") (pintype "bidirectional"))
      (node (ref "U6") (pin "P6") (pinfunction "TDO_P6") (pintype "bidirectional"))
    )
    (net (code "114") (name "TARGET_TMS{slash}SWDIO") (class "Default")
      (node (ref "U1") (pin "P$99") (pinfunction "PC1_P$99") (pintype "bidirectional"))
      (node (ref "U6") (pin "P2") (pinfunction "TMS_P2") (pintype "bidirectional"))
    )
    (net (code "115") (name "TARGET_VBUS") (class "Default")
      (node (ref "U1") (pin "P$96") (pinfunction "PB1_P$96") (pintype "bidirectional"))
    )
    (net (code "116") (name "USBD_N") (class "Default")
      (node (ref "U1") (pin "P$93") (pinfunction "PL7_P$93") (pintype "bidirectional"))
    )
    (net (code "117") (name "USBD_P") (class "Default")
      (node (ref "U1") (pin "P$94") (pinfunction "PL6_P$94") (pintype "bidirectional"))
    )
    (net (code "118") (name "unconnected-(U$1-Pad3.3V_2)") (class "Default")
      (node (ref "U$1") (pin "3.3V_2") (pinfunction "3.3V_2_3.3V_2") (pintype "bidirectional"))
    )
    (net (code "119") (name "unconnected-(U$1-Pad5V)") (class "Default")
      (node (ref "U$1") (pin "5V") (pinfunction "5V_5V") (pintype "bidirectional"))
    )
    (net (code "120") (name "unconnected-(U$1-PadINT)") (class "Default")
      (node (ref "U$1") (pin "INT") (pinfunction "INT_INT") (pintype "bidirectional"))
    )
    (net (code "121") (name "unconnected-(U1B-VBAT-PadP$68)") (class "Default")
      (node (ref "U1") (pin "P$68") (pinfunction "VBAT_P$68") (pintype "bidirectional"))
    )
    (net (code "122") (name "unconnected-(U1B-XOSC0-PadP$66)") (class "Default")
      (node (ref "U1") (pin "P$66") (pinfunction "XOSC0_P$66") (pintype "bidirectional"))
    )
    (net (code "123") (name "unconnected-(U1B-XOSC1-PadP$67)") (class "Default")
      (node (ref "U1") (pin "P$67") (pinfunction "XOSC1_P$67") (pintype "bidirectional"))
    )
    (net (code "124") (name "unconnected-(U1B-~{HIB}-PadP$65)") (class "Default")
      (node (ref "U1") (pin "P$65") (pinfunction "~{HIB}_P$65") (pintype "bidirectional"))
    )
    (net (code "125") (name "unconnected-(U1B-~{WAKE}-PadP$64)") (class "Default")
      (node (ref "U1") (pin "P$64") (pinfunction "~{WAKE}_P$64") (pintype "bidirectional"))
    )
    (net (code "126") (name "unconnected-(U6-P$7-PadP7)") (class "Default")
      (node (ref "U6") (pin "P7") (pinfunction "P$7_P7") (pintype "bidirectional"))
    )
    (net (code "127") (name "unconnected-(U6-~{EXTDBG}-PadP3)") (class "Default")
      (node (ref "U6") (pin "P3") (pinfunction "~{EXTDBG}_P3") (pintype "bidirectional"))
    )
    (net (code "128") (name "unconnected-(Y1-NC2-PadP$2)") (class "Default")
      (node (ref "Y1") (pin "P$2") (pinfunction "NC2_P$2") (pintype "bidirectional"))
    )
    (net (code "129") (name "unconnected-(Y1-NC4-PadP$4)") (class "Default")
      (node (ref "Y1") (pin "P$4") (pinfunction "NC4_P$4") (pintype "bidirectional"))
    )
    (net (code "130") (name "~{TARGET_RESET}") (class "Default")
      (node (ref "R51") (pin "1") (pinfunction "1_1") (pintype "passive"))
      (node (ref "RESET") (pin "P$3") (pinfunction "1_P$3") (pintype "passive"))
      (node (ref "RESET") (pin "P$4") (pinfunction "1_P$4") (pintype "passive"))
      (node (ref "U6") (pin "P10") (pinfunction "~{RESET}_P10") (pintype "bidirectional"))
    )
  )
)
